# CBI_SMD_v1_3.net
KiCad netlist of a schematic drawn in EAGLE
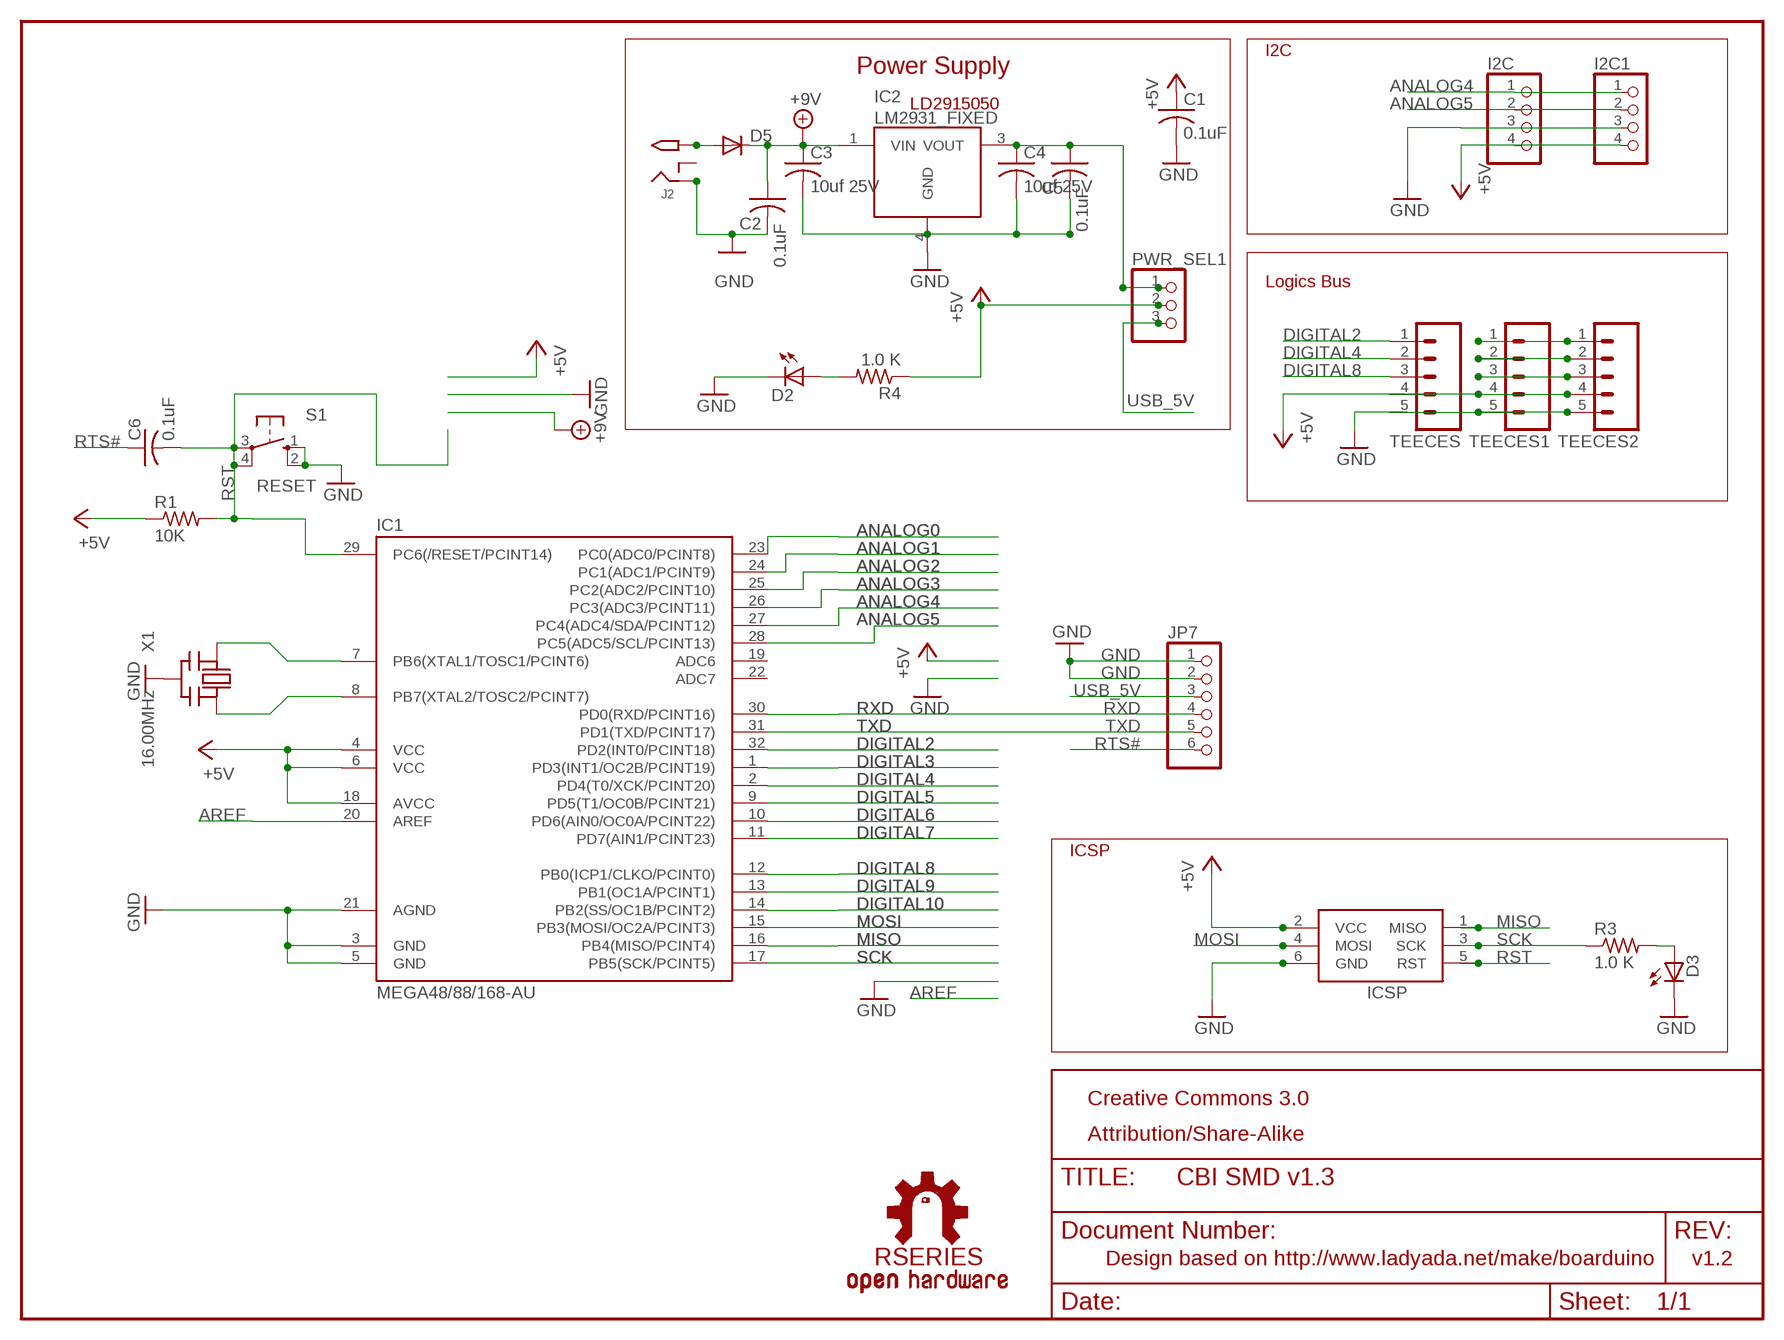
[diagram p0: schematic, sheet 1]

(export (version "E")
  (design (tool "Eeschema 10.0.6"))
  (components
    (comp (ref "C1")
      (value "0.1uF")
      (footprint "eagle-import:C1206K")
      (libsource (lib "eagle-import") (part "C-USC1206K"))
    )
    (comp (ref "C2")
      (value "0.1uF")
      (footprint "eagle-import:C1206K")
      (libsource (lib "eagle-import") (part "C-USC1206K"))
    )
    (comp (ref "C3")
      (value "10uf 25V")
      (footprint "eagle-import:C1206K")
      (libsource (lib "eagle-import") (part "rcl_C-USC1206K"))
    )
    (comp (ref "C4")
      (value "10uf 25V")
      (footprint "eagle-import:C1206K")
      (libsource (lib "eagle-import") (part "rcl_C-USC1206K"))
    )
    (comp (ref "C5")
      (value "0.1uF")
      (footprint "eagle-import:C1206K")
      (libsource (lib "eagle-import") (part "C-USC1206K"))
    )
    (comp (ref "C6")
      (value "0.1uF")
      (footprint "eagle-import:C1206K")
      (libsource (lib "eagle-import") (part "C-USC1206K"))
    )
    (comp (ref "D2")
      (value "LEDCHIPLED_1206")
      (footprint "eagle-import:CHIPLED_1206")
      (libsource (lib "eagle-import") (part "LEDCHIPLED_1206"))
    )
    (comp (ref "D3")
      (value "Green")
      (footprint "eagle-import:CHIPLED_1206")
      (libsource (lib "eagle-import") (part "LEDCHIPLED_1206"))
    )
    (comp (ref "D5")
      (value "DIODE-SMB")
      (footprint "eagle-import:SMB")
      (libsource (lib "eagle-import") (part "DIODE-SMB"))
    )
    (comp (ref "I2C")
      (value "PINHD-1X4CB")
      (footprint "eagle-import:1X04-CB")
      (libsource (lib "eagle-import") (part "PINHD-1X4CB"))
    )
    (comp (ref "I2C1")
      (value "PINHD-1X4CB")
      (footprint "eagle-import:1X04-CB")
      (libsource (lib "eagle-import") (part "PINHD-1X4CB"))
    )
    (comp (ref "IC1")
      (value "MEGA48/88/168-AU")
      (footprint "eagle-import:TQFP32-08")
      (libsource (lib "eagle-import") (part "MEGA48/88/168-AU"))
    )
    (comp (ref "IC2")
      (value "LM2931_FIXED")
      (footprint "eagle-import:DPAK")
      (libsource (lib "eagle-import") (part "LM2931_FIXED"))
    )
    (comp (ref "ICSP")
      (value "AVRISP-6")
      (footprint "eagle-import:AVRISP")
      (libsource (lib "eagle-import") (part "AVRISP-6"))
    )
    (comp (ref "J2")
      (value "2.1MMJACK")
      (footprint "eagle-import:PJ-102A")
      (libsource (lib "eagle-import") (part "2.1MMJACK"))
    )
    (comp (ref "JP7")
      (value "PINHD-1X6CLEAN")
      (footprint "eagle-import:1X06-CLEAN")
      (libsource (lib "eagle-import") (part "PINHD-1X6CLEAN"))
    )
    (comp (ref "PWR_SEL1")
      (value "PINHD-1X3")
      (footprint "eagle-import:1X03")
      (libsource (lib "eagle-import") (part "PINHD-1X3"))
    )
    (comp (ref "R1")
      (value "10K")
      (footprint "eagle-import:R1206")
      (libsource (lib "eagle-import") (part "rcl-ez_R-US_R1206"))
    )
    (comp (ref "R3")
      (value "1.0 K")
      (footprint "eagle-import:M1206")
      (libsource (lib "eagle-import") (part "R-US_M1206"))
    )
    (comp (ref "R4")
      (value "1.0 K")
      (footprint "eagle-import:M1206")
      (libsource (lib "eagle-import") (part "R-US_M1206"))
    )
    (comp (ref "S1")
      (value "RESET")
      (footprint "eagle-import:B3F-10XX")
      (libsource (lib "eagle-import") (part "10-XX"))
    )
    (comp (ref "TEECES")
      (value "M05PTH")
      (footprint "eagle-import:1X05")
      (libsource (lib "eagle-import") (part "M05PTH"))
    )
    (comp (ref "TEECES1")
      (value "M05PTH")
      (footprint "eagle-import:1X05")
      (libsource (lib "eagle-import") (part "M05PTH"))
    )
    (comp (ref "TEECES2")
      (value "M05PTH")
      (footprint "eagle-import:1X05")
      (libsource (lib "eagle-import") (part "M05PTH"))
    )
    (comp (ref "U$2")
      (value "RSERIES-OSHW-LOGOMEDIUM")
      (footprint "eagle-import:RSERIES-OSHW-LOGO-MEDIUM")
      (libsource (lib "eagle-import") (part "RSERIES-OSHW-LOGOMEDIUM"))
    )
    (comp (ref "X1")
      (value "16.00MHz")
      (footprint "eagle-import:CERM_OSC")
      (libsource (lib "eagle-import") (part "CERMOSCILL"))
    )
  )
  (nets
    (net (code "1") (name "+5V") (class "Default")
      (node (ref "C1") (pin "1") (pinfunction "1_1") (pintype "passive"))
      (node (ref "I2C") (pin "4") (pinfunction "4_4") (pintype "passive"))
      (node (ref "I2C1") (pin "4") (pinfunction "4_4") (pintype "passive"))
      (node (ref "IC1") (pin "18") (pinfunction "AVCC_18") (pintype "passive"))
      (node (ref "IC1") (pin "4") (pinfunction "VCC_4") (pintype "power_in"))
      (node (ref "IC1") (pin "6") (pinfunction "VCC_6") (pintype "power_in"))
      (node (ref "ICSP") (pin "2") (pinfunction "VCC_2") (pintype "power_in"))
      (node (ref "PWR_SEL1") (pin "2") (pinfunction "2_2") (pintype "passive"))
      (node (ref "R1") (pin "1") (pinfunction "1_1") (pintype "passive"))
      (node (ref "R4") (pin "1") (pinfunction "1_1") (pintype "passive"))
      (node (ref "TEECES") (pin "4") (pinfunction "4_4") (pintype "passive"))
      (node (ref "TEECES1") (pin "4") (pinfunction "4_4") (pintype "passive"))
      (node (ref "TEECES2") (pin "4") (pinfunction "4_4") (pintype "passive"))
    )
    (net (code "2") (name "+9V") (class "Default")
      (node (ref "C2") (pin "1") (pinfunction "1_1") (pintype "passive"))
      (node (ref "C3") (pin "1") (pinfunction "1_1") (pintype "passive"))
      (node (ref "D5") (pin "C") (pinfunction "C_C") (pintype "passive"))
      (node (ref "IC2") (pin "1") (pinfunction "VIN_1") (pintype "bidirectional"))
    )
    (net (code "3") (name "/ANALOG0") (class "Default")
      (node (ref "IC1") (pin "23") (pinfunction "PC0(ADC0/PCINT8)_23") (pintype "bidirectional"))
    )
    (net (code "4") (name "/ANALOG1") (class "Default")
      (node (ref "IC1") (pin "24") (pinfunction "PC1(ADC1/PCINT9)_24") (pintype "bidirectional"))
    )
    (net (code "5") (name "/ANALOG2") (class "Default")
      (node (ref "IC1") (pin "25") (pinfunction "PC2(ADC2/PCINT10)_25") (pintype "bidirectional"))
    )
    (net (code "6") (name "/ANALOG3") (class "Default")
      (node (ref "IC1") (pin "26") (pinfunction "PC3(ADC3/PCINT11)_26") (pintype "bidirectional"))
    )
    (net (code "7") (name "/ANALOG4") (class "Default")
      (node (ref "I2C") (pin "1") (pinfunction "1_1") (pintype "passive"))
      (node (ref "I2C1") (pin "1") (pinfunction "1_1") (pintype "passive"))
      (node (ref "IC1") (pin "27") (pinfunction "PC4(ADC4/SDA/PCINT12)_27") (pintype "bidirectional"))
    )
    (net (code "8") (name "/ANALOG5") (class "Default")
      (node (ref "I2C") (pin "2") (pinfunction "2_2") (pintype "passive"))
      (node (ref "I2C1") (pin "2") (pinfunction "2_2") (pintype "passive"))
      (node (ref "IC1") (pin "28") (pinfunction "PC5(ADC5/SCL/PCINT13)_28") (pintype "bidirectional"))
    )
    (net (code "9") (name "/AREF") (class "Default")
      (node (ref "IC1") (pin "20") (pinfunction "AREF_20") (pintype "passive"))
    )
    (net (code "10") (name "/DIGITAL2") (class "Default")
      (node (ref "IC1") (pin "32") (pinfunction "PD2(INT0/PCINT18)_32") (pintype "bidirectional"))
      (node (ref "TEECES") (pin "1") (pinfunction "1_1") (pintype "passive"))
    )
    (net (code "11") (name "/DIGITAL3") (class "Default")
      (node (ref "IC1") (pin "1") (pinfunction "PD3(INT1/OC2B/PCINT19)_1") (pintype "bidirectional"))
    )
    (net (code "12") (name "/DIGITAL4") (class "Default")
      (node (ref "IC1") (pin "2") (pinfunction "PD4(T0/XCK/PCINT20)_2") (pintype "bidirectional"))
      (node (ref "TEECES") (pin "2") (pinfunction "2_2") (pintype "passive"))
    )
    (net (code "13") (name "/DIGITAL5") (class "Default")
      (node (ref "IC1") (pin "9") (pinfunction "PD5(T1/OC0B/PCINT21)_9") (pintype "bidirectional"))
    )
    (net (code "14") (name "/DIGITAL6") (class "Default")
      (node (ref "IC1") (pin "10") (pinfunction "PD6(AIN0/OC0A/PCINT22)_10") (pintype "bidirectional"))
    )
    (net (code "15") (name "/DIGITAL7") (class "Default")
      (node (ref "IC1") (pin "11") (pinfunction "PD7(AIN1/PCINT23)_11") (pintype "bidirectional"))
    )
    (net (code "16") (name "/DIGITAL8") (class "Default")
      (node (ref "IC1") (pin "12") (pinfunction "PB0(ICP1/CLKO/PCINT0)_12") (pintype "bidirectional"))
      (node (ref "TEECES") (pin "3") (pinfunction "3_3") (pintype "passive"))
    )
    (net (code "17") (name "/DIGITAL9") (class "Default")
      (node (ref "IC1") (pin "13") (pinfunction "PB1(OC1A/PCINT1)_13") (pintype "bidirectional"))
    )
    (net (code "18") (name "/DIGITAL10") (class "Default")
      (node (ref "IC1") (pin "14") (pinfunction "PB2(SS/OC1B/PCINT2)_14") (pintype "bidirectional"))
    )
    (net (code "19") (name "/MISO") (class "Default")
      (node (ref "IC1") (pin "16") (pinfunction "PB4(MISO/PCINT4)_16") (pintype "bidirectional"))
      (node (ref "ICSP") (pin "1") (pinfunction "MISO_1") (pintype "input"))
    )
    (net (code "20") (name "/MOSI") (class "Default")
      (node (ref "IC1") (pin "15") (pinfunction "PB3(MOSI/OC2A/PCINT3)_15") (pintype "bidirectional"))
      (node (ref "ICSP") (pin "4") (pinfunction "MOSI_4") (pintype "output"))
    )
    (net (code "21") (name "/RST") (class "Default")
      (node (ref "C6") (pin "2") (pinfunction "2_2") (pintype "passive"))
      (node (ref "IC1") (pin "29") (pinfunction "PC6(/RESET/PCINT14)_29") (pintype "bidirectional"))
      (node (ref "ICSP") (pin "5") (pinfunction "RST_5") (pintype "output"))
      (node (ref "R1") (pin "2") (pinfunction "2_2") (pintype "passive"))
      (node (ref "S1") (pin "3") (pinfunction "P_3") (pintype "passive"))
      (node (ref "S1") (pin "4") (pinfunction "P1_4") (pintype "passive"))
    )
    (net (code "22") (name "/RTS#") (class "Default")
      (node (ref "C6") (pin "1") (pinfunction "1_1") (pintype "passive"))
      (node (ref "JP7") (pin "6") (pinfunction "6_6") (pintype "passive"))
    )
    (net (code "23") (name "/RXD") (class "Default")
      (node (ref "IC1") (pin "30") (pinfunction "PD0(RXD/PCINT16)_30") (pintype "bidirectional"))
      (node (ref "JP7") (pin "4") (pinfunction "4_4") (pintype "passive"))
    )
    (net (code "24") (name "/SCK") (class "Default")
      (node (ref "IC1") (pin "17") (pinfunction "PB5(SCK/PCINT5)_17") (pintype "bidirectional"))
      (node (ref "ICSP") (pin "3") (pinfunction "SCK_3") (pintype "output"))
      (node (ref "R3") (pin "1") (pinfunction "1_1") (pintype "passive"))
    )
    (net (code "25") (name "/TXD") (class "Default")
      (node (ref "IC1") (pin "31") (pinfunction "PD1(TXD/PCINT17)_31") (pintype "bidirectional"))
      (node (ref "JP7") (pin "5") (pinfunction "5_5") (pintype "passive"))
    )
    (net (code "26") (name "/USB_5V") (class "Default")
      (node (ref "JP7") (pin "3") (pinfunction "3_3") (pintype "passive"))
      (node (ref "PWR_SEL1") (pin "3") (pinfunction "3_3") (pintype "passive"))
    )
    (net (code "27") (name "GND") (class "Default")
      (node (ref "C1") (pin "2") (pinfunction "2_2") (pintype "passive"))
      (node (ref "C2") (pin "2") (pinfunction "2_2") (pintype "passive"))
      (node (ref "D2") (pin "C") (pinfunction "C_C") (pintype "passive"))
      (node (ref "D3") (pin "C") (pinfunction "C_C") (pintype "passive"))
      (node (ref "I2C") (pin "3") (pinfunction "3_3") (pintype "passive"))
      (node (ref "I2C1") (pin "3") (pinfunction "3_3") (pintype "passive"))
      (node (ref "IC1") (pin "21") (pinfunction "AGND_21") (pintype "power_in"))
      (node (ref "IC1") (pin "3") (pinfunction "GND_3") (pintype "power_in"))
      (node (ref "IC1") (pin "5") (pinfunction "GND_5") (pintype "power_in"))
      (node (ref "IC2") (pin "4") (pinfunction "GND_4") (pintype "bidirectional"))
      (node (ref "ICSP") (pin "6") (pinfunction "GND_6") (pintype "power_in"))
      (node (ref "J2") (pin "RING") (pinfunction "RING_RING") (pintype "bidirectional"))
      (node (ref "JP7") (pin "1") (pinfunction "1_1") (pintype "passive"))
      (node (ref "JP7") (pin "2") (pinfunction "2_2") (pintype "passive"))
      (node (ref "S1") (pin "1") (pinfunction "S_1") (pintype "passive"))
      (node (ref "S1") (pin "2") (pinfunction "S1_2") (pintype "passive"))
      (node (ref "TEECES") (pin "5") (pinfunction "5_5") (pintype "passive"))
      (node (ref "TEECES1") (pin "5") (pinfunction "5_5") (pintype "passive"))
      (node (ref "TEECES2") (pin "5") (pinfunction "5_5") (pintype "passive"))
      (node (ref "X1") (pin "P$2") (pinfunction "GND_P$2") (pintype "bidirectional"))
    )
    (net (code "28") (name "Net-(C3-Pad2)") (class "Default")
      (node (ref "C3") (pin "2") (pinfunction "2_2") (pintype "passive"))
      (node (ref "C4") (pin "2") (pinfunction "2_2") (pintype "passive"))
      (node (ref "C5") (pin "2") (pinfunction "2_2") (pintype "passive"))
    )
    (net (code "29") (name "Net-(D2-PadA)") (class "Default")
      (node (ref "D2") (pin "A") (pinfunction "A_A") (pintype "passive"))
      (node (ref "R4") (pin "2") (pinfunction "2_2") (pintype "passive"))
    )
    (net (code "30") (name "Net-(D3-PadA)") (class "Default")
      (node (ref "D3") (pin "A") (pinfunction "A_A") (pintype "passive"))
      (node (ref "R3") (pin "2") (pinfunction "2_2") (pintype "passive"))
    )
    (net (code "31") (name "Net-(D5-PadA)") (class "Default")
      (node (ref "D5") (pin "A") (pinfunction "A_A") (pintype "passive"))
      (node (ref "J2") (pin "TIP") (pinfunction "TIP_TIP") (pintype "bidirectional"))
    )
    (net (code "32") (name "Net-(IC1-PB6(XTAL1{slash}TOSC1{slash}PCINT6))") (class "Default")
      (node (ref "IC1") (pin "7") (pinfunction "PB6(XTAL1/TOSC1/PCINT6)_7") (pintype "bidirectional"))
      (node (ref "X1") (pin "P$1") (pinfunction "IN_P$1") (pintype "bidirectional"))
    )
    (net (code "33") (name "Net-(IC1-PB7(XTAL2{slash}TOSC2{slash}PCINT7))") (class "Default")
      (node (ref "IC1") (pin "8") (pinfunction "PB7(XTAL2/TOSC2/PCINT7)_8") (pintype "bidirectional"))
      (node (ref "X1") (pin "P$3") (pinfunction "OUT_P$3") (pintype "bidirectional"))
    )
    (net (code "34") (name "Net-(IC2-VOUT)") (class "Default")
      (node (ref "C4") (pin "1") (pinfunction "1_1") (pintype "passive"))
      (node (ref "C5") (pin "1") (pinfunction "1_1") (pintype "passive"))
      (node (ref "IC2") (pin "3") (pinfunction "VOUT_3") (pintype "bidirectional"))
      (node (ref "PWR_SEL1") (pin "1") (pinfunction "1_1") (pintype "passive"))
    )
    (net (code "35") (name "Net-(TEECES1-Pad1)") (class "Default")
      (node (ref "TEECES1") (pin "1") (pinfunction "1_1") (pintype "passive"))
      (node (ref "TEECES2") (pin "1") (pinfunction "1_1") (pintype "passive"))
    )
    (net (code "36") (name "Net-(TEECES1-Pad2)") (class "Default")
      (node (ref "TEECES1") (pin "2") (pinfunction "2_2") (pintype "passive"))
      (node (ref "TEECES2") (pin "2") (pinfunction "2_2") (pintype "passive"))
    )
    (net (code "37") (name "Net-(TEECES1-Pad3)") (class "Default")
      (node (ref "TEECES1") (pin "3") (pinfunction "3_3") (pintype "passive"))
      (node (ref "TEECES2") (pin "3") (pinfunction "3_3") (pintype "passive"))
    )
    (net (code "38") (name "unconnected-(IC1-ADC6-Pad19)") (class "Default")
      (node (ref "IC1") (pin "19") (pinfunction "ADC6_19") (pintype "passive"))
    )
    (net (code "39") (name "unconnected-(IC1-ADC7-Pad22)") (class "Default")
      (node (ref "IC1") (pin "22") (pinfunction "ADC7_22") (pintype "passive"))
    )
    (net (code "40") (name "unconnected-(J2-PadRING_SW)") (class "Default")
      (node (ref "J2") (pin "RING_SW") (pinfunction "RING_SW_RING_SW") (pintype "bidirectional"))
    )
  )
)
